# 7_Segment_Display.net
KiCad netlist of a schematic drawn in Altium Designer
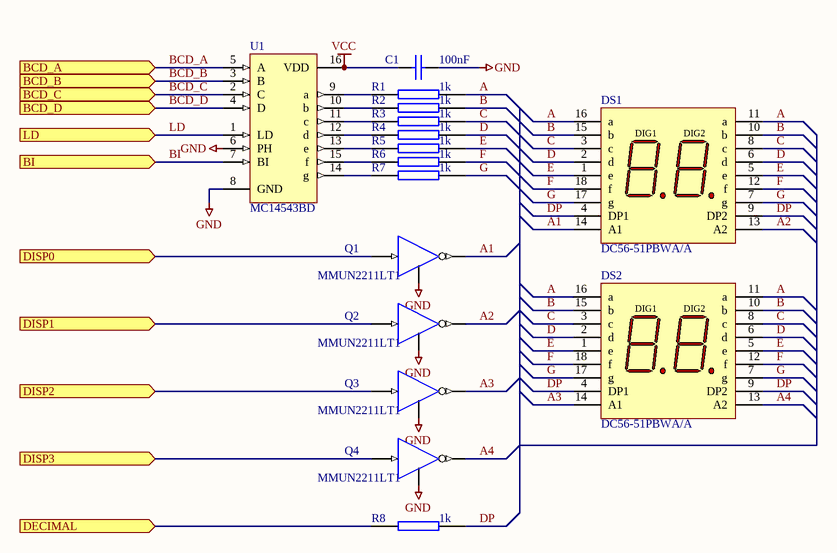
[diagram p0: 7 Segment Display.SchDoc]

(export (version "E")
  (design (tool "Eeschema 10.0.6"))
  (components
    (comp (ref "C1")
      (value "100nF")
      (footprint "CAP (3D) - 0603")
      (description "CAPACITOR SMD 0603")
      (fields (field (name "MOUSER PART NO.") "81-GCM188R71C104KA7D") (field (name "MANUFACTURER") "Murata"))
      (libsource (lib "NASCO Capacitors") (part "CAP SMD 0603 100nF"))
    )
    (comp (ref "DS1")
      (value "DC56-51PBWA/A")
      (footprint "K-18 (3D)")
      (description "14.22 mm 2-Digit General Purpose Blue 7-Segment Display")
      (fields (field (name "MANUFACTURER") "Kingbright") (field (name "MOUSER PART NO.") "604-DC56-51PWA/A"))
      (libsource (lib "Agilent LED Display 7-Segment, 2-Digit") (part "HDSP-521A"))
    )
    (comp (ref "DS2")
      (value "DC56-51PBWA/A")
      (footprint "K-18 (3D)")
      (description "14.22 mm 2-Digit General Purpose Blue 7-Segment Display")
      (fields (field (name "MANUFACTURER") "Kingbright") (field (name "MOUSER PART NO.") "604-DC56-51PWA/A"))
      (libsource (lib "Agilent LED Display 7-Segment, 2-Digit") (part "HDSP-521A"))
    )
    (comp (ref "Q1")
      (value "MMUN2211LT1")
      (footprint "SOT23-3L")
      (fields
        (field (name "MOUSER PART NO.") "863-MUN5211T1G")
        (field (name "MANUFACTURER") "ON Semiconductor")
        (field (name "MANUFACTURER PART NO.") "MUN5211T1G")
      )
      (libsource (lib "401 CCPA") (part "NPN DIGITAL TRANSISTOR"))
    )
    (comp (ref "Q2")
      (value "MMUN2211LT1")
      (footprint "SOT23-3L")
      (fields
        (field (name "MOUSER PART NO.") "863-MUN5211T1G")
        (field (name "MANUFACTURER") "ON Semiconductor")
        (field (name "MANUFACTURER PART NO.") "MUN5211T1G")
      )
      (libsource (lib "401 CCPA") (part "NPN DIGITAL TRANSISTOR"))
    )
    (comp (ref "Q3")
      (value "MMUN2211LT1")
      (footprint "SOT23-3L")
      (fields
        (field (name "MOUSER PART NO.") "863-MUN5211T1G")
        (field (name "MANUFACTURER") "ON Semiconductor")
        (field (name "MANUFACTURER PART NO.") "MUN5211T1G")
      )
      (libsource (lib "401 CCPA") (part "NPN DIGITAL TRANSISTOR"))
    )
    (comp (ref "Q4")
      (value "MMUN2211LT1")
      (footprint "SOT23-3L")
      (fields
        (field (name "MOUSER PART NO.") "863-MUN5211T1G")
        (field (name "MANUFACTURER") "ON Semiconductor")
        (field (name "MANUFACTURER PART NO.") "MUN5211T1G")
      )
      (libsource (lib "401 CCPA") (part "NPN DIGITAL TRANSISTOR"))
    )
    (comp (ref "R1")
      (value "1k")
      (footprint "RES (3D) - 0603")
      (description "RESISTOR SMD 0603 1k")
      (fields (field (name "MOUSER PART NO.") "652-CR0603-JW-102ELF") (field (name "MANUFACTURER") "Bourns"))
      (libsource (lib "NASCO Resistors") (part "RES SMD 0603 1k"))
    )
    (comp (ref "R2")
      (value "1k")
      (footprint "RES (3D) - 0603")
      (description "RESISTOR SMD 0603 1k")
      (fields (field (name "MOUSER PART NO.") "652-CR0603-JW-102ELF") (field (name "MANUFACTURER") "Bourns"))
      (libsource (lib "NASCO Resistors") (part "RES SMD 0603 1k"))
    )
    (comp (ref "R3")
      (value "1k")
      (footprint "RES (3D) - 0603")
      (description "RESISTOR SMD 0603 1k")
      (fields (field (name "MOUSER PART NO.") "652-CR0603-JW-102ELF") (field (name "MANUFACTURER") "Bourns"))
      (libsource (lib "NASCO Resistors") (part "RES SMD 0603 1k"))
    )
    (comp (ref "R4")
      (value "1k")
      (footprint "RES (3D) - 0603")
      (description "RESISTOR SMD 0603 1k")
      (fields (field (name "MOUSER PART NO.") "652-CR0603-JW-102ELF") (field (name "MANUFACTURER") "Bourns"))
      (libsource (lib "NASCO Resistors") (part "RES SMD 0603 1k"))
    )
    (comp (ref "R5")
      (value "1k")
      (footprint "RES (3D) - 0603")
      (description "RESISTOR SMD 0603 1k")
      (fields (field (name "MOUSER PART NO.") "652-CR0603-JW-102ELF") (field (name "MANUFACTURER") "Bourns"))
      (libsource (lib "NASCO Resistors") (part "RES SMD 0603 1k"))
    )
    (comp (ref "R6")
      (value "1k")
      (footprint "RES (3D) - 0603")
      (description "RESISTOR SMD 0603 1k")
      (fields (field (name "MOUSER PART NO.") "652-CR0603-JW-102ELF") (field (name "MANUFACTURER") "Bourns"))
      (libsource (lib "NASCO Resistors") (part "RES SMD 0603 1k"))
    )
    (comp (ref "R7")
      (value "1k")
      (footprint "RES (3D) - 0603")
      (description "RESISTOR SMD 0603 1k")
      (fields (field (name "MOUSER PART NO.") "652-CR0603-JW-102ELF") (field (name "MANUFACTURER") "Bourns"))
      (libsource (lib "NASCO Resistors") (part "RES SMD 0603 1k"))
    )
    (comp (ref "R8")
      (value "1k")
      (footprint "RES (3D) - 0603")
      (description "RESISTOR SMD 0603 1k")
      (fields (field (name "MOUSER PART NO.") "652-CR0603-JW-102ELF") (field (name "MANUFACTURER") "Bourns"))
      (libsource (lib "NASCO Resistors") (part "RES SMD 0603 1k"))
    )
    (comp (ref "U1")
      (value "MC14543BD")
      (footprint "751B-05_N")
      (description "BCD-to-7-Segment Latch/Decoder/Driver for Liquid Crystals")
      (fields
        (field (name "MANUFACTURER") "TEXAS INSTRUMENTS")
        (field (name "MANUFACTURER PART NO.") "CD4543BPWR")
      )
      (libsource (lib "ON Semi Interface Display Driver") (part "MC14543BD"))
    )
  )
  (nets
    (net (code "1") (name "/A") (class "Default")
      (node (ref "DS1") (pin "11") (pinfunction "a_11") (pintype "passive"))
      (node (ref "DS1") (pin "16") (pinfunction "a_16") (pintype "passive"))
      (node (ref "DS2") (pin "11") (pinfunction "a_11") (pintype "passive"))
      (node (ref "DS2") (pin "16") (pinfunction "a_16") (pintype "passive"))
      (node (ref "R1") (pin "2") (pinfunction "2_2") (pintype "passive"))
    )
    (net (code "2") (name "/A1") (class "Default")
      (node (ref "DS1") (pin "14") (pinfunction "A1_14") (pintype "passive"))
      (node (ref "Q1") (pin "3") (pinfunction "C_3") (pintype "output"))
    )
    (net (code "3") (name "/A2") (class "Default")
      (node (ref "DS1") (pin "13") (pinfunction "A2_13") (pintype "passive"))
      (node (ref "Q2") (pin "3") (pinfunction "C_3") (pintype "output"))
    )
    (net (code "4") (name "/A3") (class "Default")
      (node (ref "DS2") (pin "14") (pinfunction "A1_14") (pintype "passive"))
      (node (ref "Q3") (pin "3") (pinfunction "C_3") (pintype "output"))
    )
    (net (code "5") (name "/A4") (class "Default")
      (node (ref "DS2") (pin "13") (pinfunction "A2_13") (pintype "passive"))
      (node (ref "Q4") (pin "3") (pinfunction "C_3") (pintype "output"))
    )
    (net (code "6") (name "/B") (class "Default")
      (node (ref "DS1") (pin "10") (pinfunction "b_10") (pintype "passive"))
      (node (ref "DS1") (pin "15") (pinfunction "b_15") (pintype "passive"))
      (node (ref "DS2") (pin "10") (pinfunction "b_10") (pintype "passive"))
      (node (ref "DS2") (pin "15") (pinfunction "b_15") (pintype "passive"))
      (node (ref "R2") (pin "2") (pinfunction "2_2") (pintype "passive"))
    )
    (net (code "7") (name "/BCD_A") (class "Default")
      (node (ref "U1") (pin "5") (pinfunction "A_5") (pintype "input"))
    )
    (net (code "8") (name "/BCD_B") (class "Default")
      (node (ref "U1") (pin "3") (pinfunction "B_3") (pintype "input"))
    )
    (net (code "9") (name "/BCD_C") (class "Default")
      (node (ref "U1") (pin "2") (pinfunction "C_2") (pintype "input"))
    )
    (net (code "10") (name "/BCD_D") (class "Default")
      (node (ref "U1") (pin "4") (pinfunction "D_4") (pintype "input"))
    )
    (net (code "11") (name "/BI") (class "Default")
      (node (ref "U1") (pin "7") (pinfunction "BI_7") (pintype "input"))
    )
    (net (code "12") (name "/C") (class "Default")
      (node (ref "DS1") (pin "3") (pinfunction "c_3") (pintype "passive"))
      (node (ref "DS1") (pin "8") (pinfunction "c_8") (pintype "passive"))
      (node (ref "DS2") (pin "3") (pinfunction "c_3") (pintype "passive"))
      (node (ref "DS2") (pin "8") (pinfunction "c_8") (pintype "passive"))
      (node (ref "R3") (pin "2") (pinfunction "2_2") (pintype "passive"))
    )
    (net (code "13") (name "/D") (class "Default")
      (node (ref "DS1") (pin "2") (pinfunction "d_2") (pintype "passive"))
      (node (ref "DS1") (pin "6") (pinfunction "d_6") (pintype "passive"))
      (node (ref "DS2") (pin "2") (pinfunction "d_2") (pintype "passive"))
      (node (ref "DS2") (pin "6") (pinfunction "d_6") (pintype "passive"))
      (node (ref "R4") (pin "2") (pinfunction "2_2") (pintype "passive"))
    )
    (net (code "14") (name "/DECIMAL") (class "Default")
      (node (ref "R8") (pin "1") (pinfunction "1_1") (pintype "passive"))
    )
    (net (code "15") (name "/DISP0") (class "Default")
      (node (ref "Q1") (pin "1") (pinfunction "B_1") (pintype "input"))
    )
    (net (code "16") (name "/DISP1") (class "Default")
      (node (ref "Q2") (pin "1") (pinfunction "B_1") (pintype "input"))
    )
    (net (code "17") (name "/DISP2") (class "Default")
      (node (ref "Q3") (pin "1") (pinfunction "B_1") (pintype "input"))
    )
    (net (code "18") (name "/DISP3") (class "Default")
      (node (ref "Q4") (pin "1") (pinfunction "B_1") (pintype "input"))
    )
    (net (code "19") (name "/DP") (class "Default")
      (node (ref "DS1") (pin "4") (pinfunction "DP1_4") (pintype "passive"))
      (node (ref "DS1") (pin "9") (pinfunction "DP2_9") (pintype "passive"))
      (node (ref "DS2") (pin "4") (pinfunction "DP1_4") (pintype "passive"))
      (node (ref "DS2") (pin "9") (pinfunction "DP2_9") (pintype "passive"))
      (node (ref "R8") (pin "2") (pinfunction "2_2") (pintype "passive"))
    )
    (net (code "20") (name "/E") (class "Default")
      (node (ref "DS1") (pin "1") (pinfunction "e_1") (pintype "passive"))
      (node (ref "DS1") (pin "5") (pinfunction "e_5") (pintype "passive"))
      (node (ref "DS2") (pin "1") (pinfunction "e_1") (pintype "passive"))
      (node (ref "DS2") (pin "5") (pinfunction "e_5") (pintype "passive"))
      (node (ref "R5") (pin "2") (pinfunction "2_2") (pintype "passive"))
    )
    (net (code "21") (name "/F") (class "Default")
      (node (ref "DS1") (pin "12") (pinfunction "f_12") (pintype "passive"))
      (node (ref "DS1") (pin "18") (pinfunction "f_18") (pintype "passive"))
      (node (ref "DS2") (pin "12") (pinfunction "f_12") (pintype "passive"))
      (node (ref "DS2") (pin "18") (pinfunction "f_18") (pintype "passive"))
      (node (ref "R6") (pin "2") (pinfunction "2_2") (pintype "passive"))
    )
    (net (code "22") (name "/G") (class "Default")
      (node (ref "DS1") (pin "17") (pinfunction "g_17") (pintype "passive"))
      (node (ref "DS1") (pin "7") (pinfunction "g_7") (pintype "passive"))
      (node (ref "DS2") (pin "17") (pinfunction "g_17") (pintype "passive"))
      (node (ref "DS2") (pin "7") (pinfunction "g_7") (pintype "passive"))
      (node (ref "R7") (pin "2") (pinfunction "2_2") (pintype "passive"))
    )
    (net (code "23") (name "/LD") (class "Default")
      (node (ref "U1") (pin "1") (pinfunction "LD_1") (pintype "input"))
    )
    (net (code "24") (name "GND") (class "Default")
      (node (ref "C1") (pin "2") (pinfunction "2_2") (pintype "passive"))
      (node (ref "Q1") (pin "2") (pinfunction "E_2") (pintype "passive"))
      (node (ref "Q2") (pin "2") (pinfunction "E_2") (pintype "passive"))
      (node (ref "Q3") (pin "2") (pinfunction "E_2") (pintype "passive"))
      (node (ref "Q4") (pin "2") (pinfunction "E_2") (pintype "passive"))
      (node (ref "U1") (pin "6") (pinfunction "PH_6") (pintype "input"))
      (node (ref "U1") (pin "8") (pinfunction "GND_8") (pintype "power_in"))
    )
    (net (code "25") (name "Net-(U1-a)") (class "Default")
      (node (ref "R1") (pin "1") (pinfunction "1_1") (pintype "passive"))
      (node (ref "U1") (pin "9") (pinfunction "a_9") (pintype "output"))
    )
    (net (code "26") (name "Net-(U1-b)") (class "Default")
      (node (ref "R2") (pin "1") (pinfunction "1_1") (pintype "passive"))
      (node (ref "U1") (pin "10") (pinfunction "b_10") (pintype "output"))
    )
    (net (code "27") (name "Net-(U1-c)") (class "Default")
      (node (ref "R3") (pin "1") (pinfunction "1_1") (pintype "passive"))
      (node (ref "U1") (pin "11") (pinfunction "c_11") (pintype "output"))
    )
    (net (code "28") (name "Net-(U1-d)") (class "Default")
      (node (ref "R4") (pin "1") (pinfunction "1_1") (pintype "passive"))
      (node (ref "U1") (pin "12") (pinfunction "d_12") (pintype "output"))
    )
    (net (code "29") (name "Net-(U1-e)") (class "Default")
      (node (ref "R5") (pin "1") (pinfunction "1_1") (pintype "passive"))
      (node (ref "U1") (pin "13") (pinfunction "e_13") (pintype "output"))
    )
    (net (code "30") (name "Net-(U1-f)") (class "Default")
      (node (ref "R6") (pin "1") (pinfunction "1_1") (pintype "passive"))
      (node (ref "U1") (pin "15") (pinfunction "f_15") (pintype "output"))
    )
    (net (code "31") (name "Net-(U1-g)") (class "Default")
      (node (ref "R7") (pin "1") (pinfunction "1_1") (pintype "passive"))
      (node (ref "U1") (pin "14") (pinfunction "g_14") (pintype "output"))
    )
    (net (code "32") (name "VCC") (class "Default")
      (node (ref "C1") (pin "1") (pinfunction "1_1") (pintype "passive"))
      (node (ref "U1") (pin "16") (pinfunction "VDD_16") (pintype "power_in"))
    )
  )
)
